# Sheet3-power.net
KiCad netlist of a schematic drawn in Altium Designer
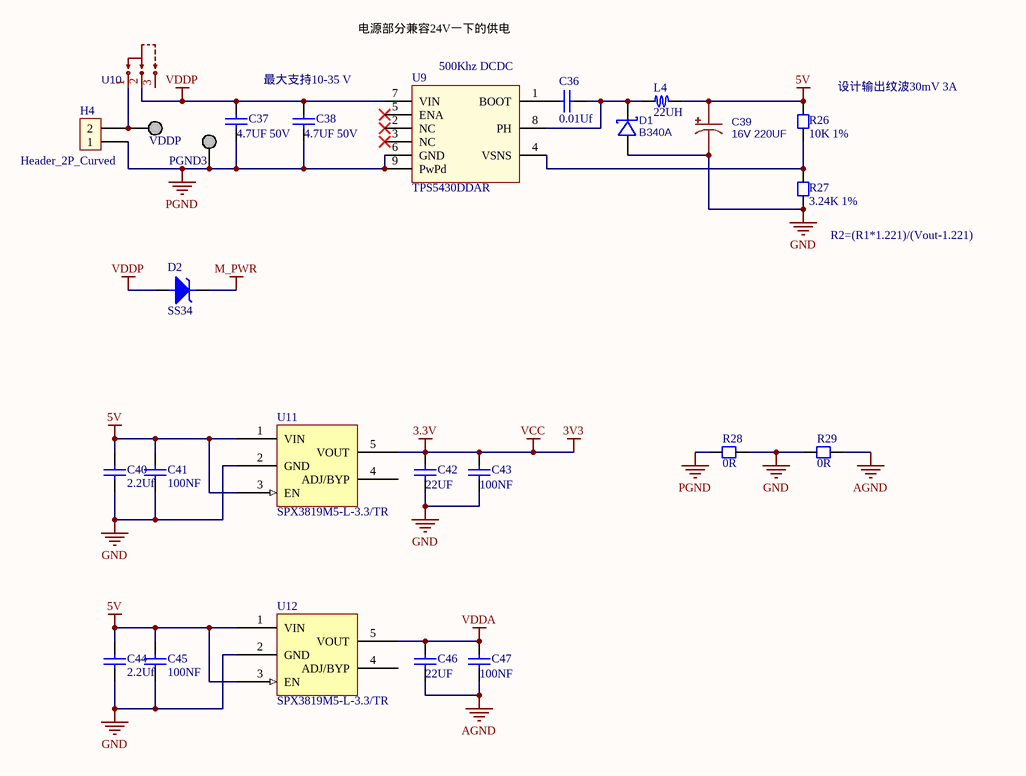
[diagram p0: Sheet3-power.SchDoc]

(export (version "E")
  (design (tool "Eeschema 10.0.6"))
  (components
    (comp (ref "C36")
      (value "0.01Uf")
      (footprint "CC1608-0603")
      (description "贴片电容")
      (libsource (lib "tianxiaohua_Schlib") (part "Chip capacitor"))
    )
    (comp (ref "C37")
      (value "4.7UF 50V")
      (footprint "CC1608-0603")
      (description "贴片电容")
      (libsource (lib "tianxiaohua_Schlib") (part "Chip capacitor"))
    )
    (comp (ref "C38")
      (value "4.7UF 50V")
      (footprint "CC1608-0603")
      (description "贴片电容")
      (libsource (lib "tianxiaohua_Schlib") (part "Chip capacitor"))
    )
    (comp (ref "C39")
      (value "16V 220UF")
      (footprint "CAP-SMD_D6.3")
      (description "铝点解电容")
      (fields
        (field (name "BOM_SUPPLIER PART") "C413527")
        (field (name "BOM_MANUFACTURER PART") "EEEFP1C681AP")
        (field (name "CONTRIBUTOR") "LCSC")
      )
      (libsource (lib "base") (part "Cap ECAP SMD"))
    )
    (comp (ref "C40")
      (value "2.2Uf")
      (footprint "CC1608-0603")
      (description "0603封装的电容")
      (fields (field (name "PUBLISHER") "Altium Limited"))
      (libsource (lib "base") (part "Cap Chip 0603"))
    )
    (comp (ref "C41")
      (value "100NF")
      (footprint "CC1608-0603")
      (description "0603封装的电容")
      (fields (field (name "PUBLISHER") "Altium Limited"))
      (libsource (lib "base") (part "Cap Chip 0603"))
    )
    (comp (ref "C42")
      (value "22UF")
      (footprint "CC1608-0603")
      (description "贴片电容")
      (libsource (lib "tianxiaohua_Schlib") (part "Chip capacitor"))
    )
    (comp (ref "C43")
      (value "100NF")
      (footprint "CC1608-0603")
      (description "贴片电容")
      (libsource (lib "tianxiaohua_Schlib") (part "Chip capacitor"))
    )
    (comp (ref "C44")
      (value "2.2Uf")
      (footprint "CC1608-0603")
      (description "0603封装的电容")
      (fields (field (name "PUBLISHER") "Altium Limited"))
      (libsource (lib "base") (part "Cap Chip 0603"))
    )
    (comp (ref "C45")
      (value "100NF")
      (footprint "CC1608-0603")
      (description "0603封装的电容")
      (fields (field (name "PUBLISHER") "Altium Limited"))
      (libsource (lib "base") (part "Cap Chip 0603"))
    )
    (comp (ref "C46")
      (value "22UF")
      (footprint "CC1608-0603")
      (description "贴片电容")
      (libsource (lib "tianxiaohua_Schlib") (part "Chip capacitor"))
    )
    (comp (ref "C47")
      (value "100NF")
      (footprint "CC1608-0603")
      (description "贴片电容")
      (libsource (lib "tianxiaohua_Schlib") (part "Chip capacitor"))
    )
    (comp (ref "D1")
      (value "B340A")
      (footprint "DO-214 AA")
      (description "40V 3A 550mV@3A")
      (fields (field (name "BOM_SUPPLIER PART") "C64982"))
      (libsource (lib "transistor") (part "B340A"))
    )
    (comp (ref "D2")
      (value "SS34")
      (footprint "DO-214 AA")
      (description "肖特基二极管")
      (libsource (lib "transistor") (part "SS34"))
    )
    (comp (ref "H4")
      (value "Header_2P_Curved")
      (footprint "Header_2_54_2PW")
      (description "弯的2P排针")
      (libsource (lib "base") (part "Header_2P_Curved"))
    )
    (comp (ref "L4")
      (value "22UH")
      (footprint "Inductor-1040")
      (description "1040封装 一体成型 贴片 功率电感")
      (libsource (lib "base") (part "Inductor-1040"))
    )
    (comp (ref "PGND3")
      (value "test")
      (footprint "test")
      (description "测试点")
      (libsource (lib "base") (part "test"))
    )
    (comp (ref "R26")
      (value "10K 1%")
      (footprint "CR1608-0603")
      (description "贴片电阻")
      (libsource (lib "tianxiaohua_Schlib") (part "Chip resistor"))
    )
    (comp (ref "R27")
      (value "3.24K 1%")
      (footprint "CR1608-0603")
      (description "贴片电阻")
      (libsource (lib "tianxiaohua_Schlib") (part "Chip resistor"))
    )
    (comp (ref "R28")
      (value "0R")
      (footprint "CR1608-0603")
      (description "0603封装电阻")
      (fields (field (name "PUBLISHER") "Altium Limited"))
      (libsource (lib "base") (part "Resistor Chip 0603"))
    )
    (comp (ref "R29")
      (value "0R")
      (footprint "CR1608-0603")
      (description "0603封装电阻")
      (fields (field (name "PUBLISHER") "Altium Limited"))
      (libsource (lib "base") (part "Resistor Chip 0603"))
    )
    (comp (ref "U9")
      (value "TPS5430DDAR")
      (footprint "SOIC-8-E")
      (description "宽电压DCDC降压IC")
      (libsource (lib "power-chip") (part "TPS5430DDAR"))
    )
    (comp (ref "U10")
      (value "HX SS12D10G4")
      (footprint "SW-TH_3P-SS12D06")
      (fields (field (name "BOM_SUPPLIER PART") "C5149841") (field (name "CONTRIBUTOR") "lcsc"))
      (libsource (lib "base") (part "SW-TH_3P-SS12D06"))
    )
    (comp (ref "U11")
      (value "SPX3819M5-L-3.3/TR")
      (footprint "SOT23-5")
      (description "LDO 3.3V , SOT-23-5 500ma")
      (libsource (lib "power-chip") (part "SPX3819M5-L-3.3/TR"))
    )
    (comp (ref "U12")
      (value "SPX3819M5-L-3.3/TR")
      (footprint "SOT23-5")
      (description "LDO 3.3V , SOT-23-5 500ma")
      (libsource (lib "power-chip") (part "SPX3819M5-L-3.3/TR"))
    )
    (comp (ref "VDDP")
      (value "test")
      (footprint "test")
      (description "测试点")
      (libsource (lib "base") (part "test"))
    )
  )
  (nets
    (net (code "1") (name "3.3V") (class "Default")
      (node (ref "C42") (pin "1") (pinfunction "1_1") (pintype "passive"))
      (node (ref "C43") (pin "1") (pinfunction "1_1") (pintype "passive"))
      (node (ref "U11") (pin "5") (pinfunction "VOUT_5") (pintype "passive"))
    )
    (net (code "2") (name "5V") (class "Default")
      (node (ref "C39") (pin "1") (pinfunction "1_1") (pintype "passive"))
      (node (ref "C40") (pin "2") (pinfunction "2_2") (pintype "passive"))
      (node (ref "C41") (pin "2") (pinfunction "2_2") (pintype "passive"))
      (node (ref "C44") (pin "2") (pinfunction "2_2") (pintype "passive"))
      (node (ref "C45") (pin "2") (pinfunction "2_2") (pintype "passive"))
      (node (ref "L4") (pin "2") (pinfunction "2_2") (pintype "passive"))
      (node (ref "R26") (pin "2") (pinfunction "2_2") (pintype "passive"))
      (node (ref "U11") (pin "1") (pinfunction "VIN_1") (pintype "power_in"))
      (node (ref "U11") (pin "3") (pinfunction "EN_3") (pintype "input"))
      (node (ref "U12") (pin "1") (pinfunction "VIN_1") (pintype "power_in"))
      (node (ref "U12") (pin "3") (pinfunction "EN_3") (pintype "input"))
    )
    (net (code "3") (name "AGND") (class "Default")
      (node (ref "C46") (pin "2") (pinfunction "2_2") (pintype "passive"))
      (node (ref "C47") (pin "2") (pinfunction "2_2") (pintype "passive"))
      (node (ref "R29") (pin "1") (pinfunction "1_1") (pintype "passive"))
    )
    (net (code "4") (name "GND") (class "Default")
      (node (ref "C39") (pin "2") (pinfunction "2_2") (pintype "passive"))
      (node (ref "C40") (pin "1") (pinfunction "1_1") (pintype "passive"))
      (node (ref "C41") (pin "1") (pinfunction "1_1") (pintype "passive"))
      (node (ref "C42") (pin "2") (pinfunction "2_2") (pintype "passive"))
      (node (ref "C43") (pin "2") (pinfunction "2_2") (pintype "passive"))
      (node (ref "C44") (pin "1") (pinfunction "1_1") (pintype "passive"))
      (node (ref "C45") (pin "1") (pinfunction "1_1") (pintype "passive"))
      (node (ref "D1") (pin "2") (pinfunction "A_2") (pintype "passive"))
      (node (ref "R27") (pin "1") (pinfunction "1_1") (pintype "passive"))
      (node (ref "R28") (pin "1") (pinfunction "1_1") (pintype "passive"))
      (node (ref "R29") (pin "2") (pinfunction "2_2") (pintype "passive"))
      (node (ref "U11") (pin "2") (pinfunction "GND_2") (pintype "power_in"))
      (node (ref "U12") (pin "2") (pinfunction "GND_2") (pintype "power_in"))
    )
    (net (code "5") (name "M_PWR") (class "Default")
      (node (ref "D2") (pin "1") (pinfunction "K_1") (pintype "passive"))
    )
    (net (code "6") (name "Net-(D1-K)") (class "Default")
      (node (ref "C36") (pin "2") (pinfunction "2_2") (pintype "passive"))
      (node (ref "D1") (pin "1") (pinfunction "K_1") (pintype "passive"))
      (node (ref "L4") (pin "1") (pinfunction "1_1") (pintype "passive"))
      (node (ref "U9") (pin "8") (pinfunction "PH_8") (pintype "passive"))
    )
    (net (code "7") (name "Net-(H4-Pad2)") (class "Default")
      (node (ref "H4") (pin "2") (pinfunction "2_2") (pintype "passive"))
      (node (ref "U10") (pin "1") (pinfunction "1_1") (pintype "passive"))
      (node (ref "VDDP") (pin "0") (pinfunction "0_0") (pintype "passive"))
    )
    (net (code "8") (name "Net-(U9-BOOT)") (class "Default")
      (node (ref "C36") (pin "1") (pinfunction "1_1") (pintype "passive"))
      (node (ref "U9") (pin "1") (pinfunction "BOOT_1") (pintype "passive"))
    )
    (net (code "9") (name "Net-(U9-VSNS)") (class "Default")
      (node (ref "R26") (pin "1") (pinfunction "1_1") (pintype "passive"))
      (node (ref "R27") (pin "2") (pinfunction "2_2") (pintype "passive"))
      (node (ref "U9") (pin "4") (pinfunction "VSNS_4") (pintype "passive"))
    )
    (net (code "10") (name "PGND") (class "Default")
      (node (ref "C37") (pin "2") (pinfunction "2_2") (pintype "passive"))
      (node (ref "C38") (pin "2") (pinfunction "2_2") (pintype "passive"))
      (node (ref "H4") (pin "1") (pinfunction "1_1") (pintype "passive"))
      (node (ref "PGND3") (pin "0") (pinfunction "0_0") (pintype "passive"))
      (node (ref "R28") (pin "2") (pinfunction "2_2") (pintype "passive"))
      (node (ref "U9") (pin "6") (pinfunction "GND_6") (pintype "passive"))
      (node (ref "U9") (pin "9") (pinfunction "PwPd_9") (pintype "passive"))
    )
    (net (code "11") (name "VDDA") (class "Default")
      (node (ref "C46") (pin "1") (pinfunction "1_1") (pintype "passive"))
      (node (ref "C47") (pin "1") (pinfunction "1_1") (pintype "passive"))
      (node (ref "U12") (pin "5") (pinfunction "VOUT_5") (pintype "passive"))
    )
    (net (code "12") (name "VDDP") (class "Default")
      (node (ref "C37") (pin "1") (pinfunction "1_1") (pintype "passive"))
      (node (ref "C38") (pin "1") (pinfunction "1_1") (pintype "passive"))
      (node (ref "D2") (pin "2") (pinfunction "A_2") (pintype "passive"))
      (node (ref "U10") (pin "2") (pinfunction "2_2") (pintype "passive"))
      (node (ref "U9") (pin "7") (pinfunction "VIN_7") (pintype "passive"))
    )
    (net (code "13") (name "unconnected-(U9-ENA-Pad5)") (class "Default")
      (node (ref "U9") (pin "5") (pinfunction "ENA_5") (pintype "passive+no_connect"))
    )
    (net (code "14") (name "unconnected-(U9-NC-Pad2)") (class "Default")
      (node (ref "U9") (pin "2") (pinfunction "NC_2") (pintype "passive+no_connect"))
    )
    (net (code "15") (name "unconnected-(U9-NC-Pad3)") (class "Default")
      (node (ref "U9") (pin "3") (pinfunction "NC_3") (pintype "passive+no_connect"))
    )
    (net (code "16") (name "unconnected-(U10-Pad3)") (class "Default")
      (node (ref "U10") (pin "3") (pinfunction "3_3") (pintype "passive"))
    )
    (net (code "17") (name "unconnected-(U11-ADJ{slash}BYP-Pad4)") (class "Default")
      (node (ref "U11") (pin "4") (pinfunction "ADJ/BYP_4") (pintype "passive"))
    )
    (net (code "18") (name "unconnected-(U12-ADJ{slash}BYP-Pad4)") (class "Default")
      (node (ref "U12") (pin "4") (pinfunction "ADJ/BYP_4") (pintype "passive"))
    )
  )
)
